# freiBot.net
KiCad netlist of a schematic drawn in EAGLE
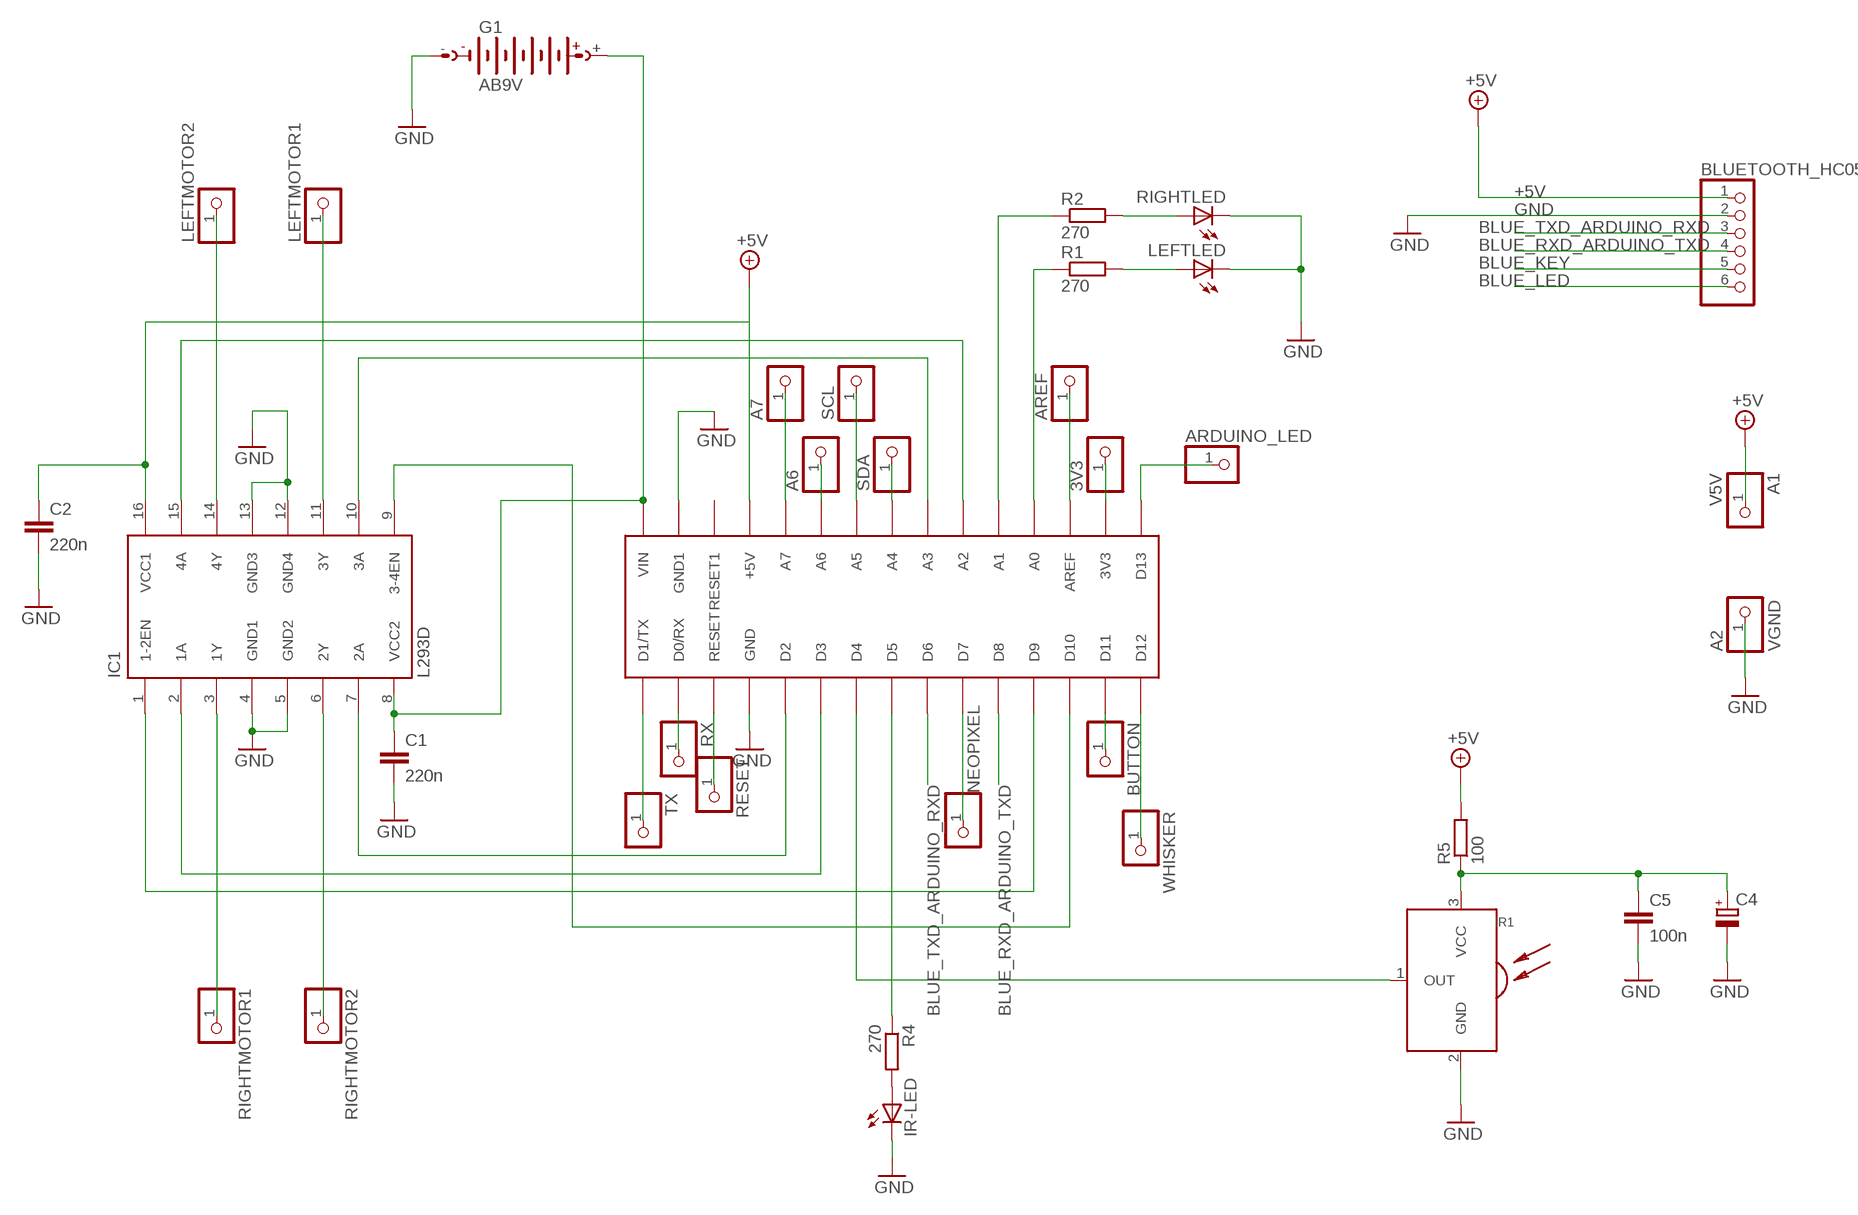
[diagram p0: schematic, sheet 1]

(export (version "E")
  (design (tool "Eeschema 10.0.6"))
  (components
    (comp (ref "3V3")
      (value "PINHD-1X1")
      (footprint "eagle-import:1X01")
      (libsource (lib "eagle-import") (part "PINHD-1X1"))
    )
    (comp (ref "A1")
      (value "V5V")
      (footprint "eagle-import:1X01")
      (libsource (lib "eagle-import") (part "PINHD-1X1"))
    )
    (comp (ref "A2")
      (value "VGND")
      (footprint "eagle-import:1X01")
      (libsource (lib "eagle-import") (part "PINHD-1X1"))
    )
    (comp (ref "A6")
      (value "PINHD-1X1")
      (footprint "eagle-import:1X01")
      (libsource (lib "eagle-import") (part "PINHD-1X1"))
    )
    (comp (ref "A7")
      (value "PINHD-1X1")
      (footprint "eagle-import:1X01")
      (libsource (lib "eagle-import") (part "PINHD-1X1"))
    )
    (comp (ref "ARDUINO_LED")
      (value "PINHD-1X1")
      (footprint "eagle-import:1X01")
      (libsource (lib "eagle-import") (part "PINHD-1X1"))
    )
    (comp (ref "AREF")
      (value "PINHD-1X1")
      (footprint "eagle-import:1X01")
      (libsource (lib "eagle-import") (part "PINHD-1X1"))
    )
    (comp (ref "BLUETOOTH_HC05")
      (value "PINHD-1X6")
      (footprint "eagle-import:1X06")
      (libsource (lib "eagle-import") (part "PINHD-1X6"))
    )
    (comp (ref "BUTTON")
      (value "PINHD-1X1")
      (footprint "eagle-import:1X01")
      (libsource (lib "eagle-import") (part "PINHD-1X1"))
    )
    (comp (ref "C1")
      (value "220n")
      (footprint "eagle-import:C075-042X103")
      (libsource (lib "eagle-import") (part "C-EU075-042X103"))
    )
    (comp (ref "C2")
      (value "220n")
      (footprint "eagle-import:C075-042X103")
      (libsource (lib "eagle-import") (part "C-EU075-042X103"))
    )
    (comp (ref "C4")
      (value "CPOL-EUE5-8.5")
      (footprint "eagle-import:E5-8,5")
      (libsource (lib "eagle-import") (part "CPOL-EUE5-8.5"))
    )
    (comp (ref "C5")
      (value "100n")
      (footprint "eagle-import:C050-025X075")
      (libsource (lib "eagle-import") (part "C-EU050-025X075"))
    )
    (comp (ref "G1")
      (value "AB9V")
      (footprint "eagle-import:AB9V")
      (libsource (lib "eagle-import") (part "AB9V"))
    )
    (comp (ref "IC1")
      (value "L293D")
      (footprint "eagle-import:DIL16")
      (libsource (lib "eagle-import") (part "L293D"))
    )
    (comp (ref "IR-LED")
      (value "LED5MM")
      (footprint "eagle-import:LED5MM")
      (libsource (lib "eagle-import") (part "LED5MM"))
    )
    (comp (ref "IR1")
      (value "SFH5110")
      (footprint "eagle-import:SFH511_")
      (libsource (lib "eagle-import") (part "SFH5110"))
    )
    (comp (ref "LEFTLED")
      (value "LED10MM")
      (footprint "eagle-import:LED10MM")
      (libsource (lib "eagle-import") (part "LED10MM"))
    )
    (comp (ref "LEFTMOTOR1")
      (value "PINHD-1X1")
      (footprint "eagle-import:1X01")
      (libsource (lib "eagle-import") (part "PINHD-1X1"))
    )
    (comp (ref "LEFTMOTOR2")
      (value "PINHD-1X1")
      (footprint "eagle-import:1X01")
      (libsource (lib "eagle-import") (part "PINHD-1X1"))
    )
    (comp (ref "NEOPIXEL")
      (value "PINHD-1X1")
      (footprint "eagle-import:1X01")
      (libsource (lib "eagle-import") (part "PINHD-1X1"))
    )
    (comp (ref "R1")
      (value "270")
      (footprint "eagle-import:0309_12")
      (libsource (lib "eagle-import") (part "R-EU_0309/12"))
    )
    (comp (ref "R2")
      (value "270")
      (footprint "eagle-import:0309_12")
      (libsource (lib "eagle-import") (part "R-EU_0309/12"))
    )
    (comp (ref "R4")
      (value "270")
      (footprint "eagle-import:0309_12")
      (libsource (lib "eagle-import") (part "R-EU_0309/12"))
    )
    (comp (ref "R5")
      (value "100")
      (footprint "eagle-import:0309_10")
      (libsource (lib "eagle-import") (part "R-EU_0309/10"))
    )
    (comp (ref "RESET")
      (value "PINHD-1X1")
      (footprint "eagle-import:1X01")
      (libsource (lib "eagle-import") (part "PINHD-1X1"))
    )
    (comp (ref "RIGHTLED")
      (value "LED10MM")
      (footprint "eagle-import:LED10MM")
      (libsource (lib "eagle-import") (part "LED10MM"))
    )
    (comp (ref "RIGHTMOTOR1")
      (value "PINHD-1X1")
      (footprint "eagle-import:1X01")
      (libsource (lib "eagle-import") (part "PINHD-1X1"))
    )
    (comp (ref "RIGHTMOTOR2")
      (value "PINHD-1X1")
      (footprint "eagle-import:1X01")
      (libsource (lib "eagle-import") (part "PINHD-1X1"))
    )
    (comp (ref "RX")
      (value "PINHD-1X1")
      (footprint "eagle-import:1X01")
      (libsource (lib "eagle-import") (part "PINHD-1X1"))
    )
    (comp (ref "SCL")
      (value "PINHD-1X1")
      (footprint "eagle-import:1X01")
      (libsource (lib "eagle-import") (part "PINHD-1X1"))
    )
    (comp (ref "SDA")
      (value "PINHD-1X1")
      (footprint "eagle-import:1X01")
      (libsource (lib "eagle-import") (part "PINHD-1X1"))
    )
    (comp (ref "TX")
      (value "PINHD-1X1")
      (footprint "eagle-import:1X01")
      (libsource (lib "eagle-import") (part "PINHD-1X1"))
    )
    (comp (ref "U$1")
      (value "ARDUINONANO")
      (footprint "eagle-import:PDIP-32")
      (libsource (lib "eagle-import") (part "ARDUINONANO"))
    )
    (comp (ref "WHISKER")
      (value "PINHD-1X1")
      (footprint "eagle-import:1X01")
      (libsource (lib "eagle-import") (part "PINHD-1X1"))
    )
  )
  (nets
    (net (code "1") (name "+5V") (class "Default")
      (node (ref "A1") (pin "1") (pinfunction "1_1") (pintype "passive"))
      (node (ref "BLUETOOTH_HC05") (pin "1") (pinfunction "1_1") (pintype "passive"))
      (node (ref "C2") (pin "1") (pinfunction "1_1") (pintype "passive"))
      (node (ref "IC1") (pin "16") (pinfunction "VCC1_16") (pintype "power_in"))
      (node (ref "R5") (pin "2") (pinfunction "2_2") (pintype "passive"))
      (node (ref "U$1") (pin "+5V") (pinfunction "+5V_+5V") (pintype "bidirectional"))
    )
    (net (code "2") (name "/BLUE_KEY") (class "Default")
      (node (ref "BLUETOOTH_HC05") (pin "5") (pinfunction "5_5") (pintype "passive"))
    )
    (net (code "3") (name "/BLUE_LED") (class "Default")
      (node (ref "BLUETOOTH_HC05") (pin "6") (pinfunction "6_6") (pintype "passive"))
    )
    (net (code "4") (name "/BLUE_RXD_ARDUINO_TXD") (class "Default")
      (node (ref "BLUETOOTH_HC05") (pin "4") (pinfunction "4_4") (pintype "passive"))
      (node (ref "U$1") (pin "D8") (pinfunction "D8_D8") (pintype "bidirectional"))
    )
    (net (code "5") (name "/BLUE_TXD_ARDUINO_RXD") (class "Default")
      (node (ref "BLUETOOTH_HC05") (pin "3") (pinfunction "3_3") (pintype "passive"))
      (node (ref "U$1") (pin "D6") (pinfunction "D6_D6") (pintype "bidirectional"))
    )
    (net (code "6") (name "GND") (class "Default")
      (node (ref "A2") (pin "1") (pinfunction "1_1") (pintype "passive"))
      (node (ref "BLUETOOTH_HC05") (pin "2") (pinfunction "2_2") (pintype "passive"))
      (node (ref "C1") (pin "2") (pinfunction "2_2") (pintype "passive"))
      (node (ref "C2") (pin "2") (pinfunction "2_2") (pintype "passive"))
      (node (ref "C4") (pin "-") (pinfunction "-_-") (pintype "passive"))
      (node (ref "C5") (pin "2") (pinfunction "2_2") (pintype "passive"))
      (node (ref "G1") (pin "-") (pinfunction "-_-") (pintype "passive"))
      (node (ref "IC1") (pin "12") (pinfunction "GND4_12") (pintype "power_in"))
      (node (ref "IC1") (pin "13") (pinfunction "GND3_13") (pintype "power_in"))
      (node (ref "IC1") (pin "4") (pinfunction "GND1_4") (pintype "power_in"))
      (node (ref "IC1") (pin "5") (pinfunction "GND2_5") (pintype "power_in"))
      (node (ref "IR-LED") (pin "K") (pinfunction "C_K") (pintype "passive"))
      (node (ref "IR1") (pin "2") (pinfunction "GND_2") (pintype "power_in"))
      (node (ref "LEFTLED") (pin "K") (pinfunction "C_K") (pintype "passive"))
      (node (ref "RIGHTLED") (pin "K") (pinfunction "C_K") (pintype "passive"))
      (node (ref "U$1") (pin "GND") (pinfunction "GND_GND") (pintype "bidirectional"))
      (node (ref "U$1") (pin "GND1") (pinfunction "GND1_GND1") (pintype "bidirectional"))
    )
    (net (code "7") (name "Net-(3V3-Pad1)") (class "Default")
      (node (ref "3V3") (pin "1") (pinfunction "1_1") (pintype "passive"))
      (node (ref "U$1") (pin "3V3") (pinfunction "3V3_3V3") (pintype "bidirectional"))
    )
    (net (code "8") (name "Net-(A6-Pad1)") (class "Default")
      (node (ref "A6") (pin "1") (pinfunction "1_1") (pintype "passive"))
      (node (ref "U$1") (pin "A6") (pinfunction "A6_A6") (pintype "bidirectional"))
    )
    (net (code "9") (name "Net-(A7-Pad1)") (class "Default")
      (node (ref "A7") (pin "1") (pinfunction "1_1") (pintype "passive"))
      (node (ref "U$1") (pin "A7") (pinfunction "A7_A7") (pintype "bidirectional"))
    )
    (net (code "10") (name "Net-(ARDUINO_LED-Pad1)") (class "Default")
      (node (ref "ARDUINO_LED") (pin "1") (pinfunction "1_1") (pintype "passive"))
      (node (ref "U$1") (pin "D13") (pinfunction "D13_D13") (pintype "bidirectional"))
    )
    (net (code "11") (name "Net-(AREF-Pad1)") (class "Default")
      (node (ref "AREF") (pin "1") (pinfunction "1_1") (pintype "passive"))
      (node (ref "U$1") (pin "AREF") (pinfunction "AREF_AREF") (pintype "bidirectional"))
    )
    (net (code "12") (name "Net-(BUTTON-Pad1)") (class "Default")
      (node (ref "BUTTON") (pin "1") (pinfunction "1_1") (pintype "passive"))
      (node (ref "U$1") (pin "D11") (pinfunction "D11_D11") (pintype "bidirectional"))
    )
    (net (code "13") (name "Net-(IC1-1-2EN)") (class "Default")
      (node (ref "IC1") (pin "1") (pinfunction "1-2EN_1") (pintype "input"))
      (node (ref "U$1") (pin "D9") (pinfunction "D9_D9") (pintype "bidirectional"))
    )
    (net (code "14") (name "Net-(IC1-1A)") (class "Default")
      (node (ref "IC1") (pin "2") (pinfunction "1A_2") (pintype "input"))
      (node (ref "U$1") (pin "D3") (pinfunction "D3_D3") (pintype "bidirectional"))
    )
    (net (code "15") (name "Net-(IC1-1Y)") (class "Default")
      (node (ref "IC1") (pin "3") (pinfunction "1Y_3") (pintype "output"))
      (node (ref "RIGHTMOTOR1") (pin "1") (pinfunction "1_1") (pintype "passive"))
    )
    (net (code "16") (name "Net-(IC1-2A)") (class "Default")
      (node (ref "IC1") (pin "7") (pinfunction "2A_7") (pintype "input"))
      (node (ref "U$1") (pin "D2") (pinfunction "D2_D2") (pintype "bidirectional"))
    )
    (net (code "17") (name "Net-(IC1-2Y)") (class "Default")
      (node (ref "IC1") (pin "6") (pinfunction "2Y_6") (pintype "output"))
      (node (ref "RIGHTMOTOR2") (pin "1") (pinfunction "1_1") (pintype "passive"))
    )
    (net (code "18") (name "Net-(IC1-3-4EN)") (class "Default")
      (node (ref "IC1") (pin "9") (pinfunction "3-4EN_9") (pintype "input"))
      (node (ref "U$1") (pin "D10") (pinfunction "D10_D10") (pintype "bidirectional"))
    )
    (net (code "19") (name "Net-(IC1-3A)") (class "Default")
      (node (ref "IC1") (pin "10") (pinfunction "3A_10") (pintype "input"))
      (node (ref "U$1") (pin "A3") (pinfunction "A3_A3") (pintype "bidirectional"))
    )
    (net (code "20") (name "Net-(IC1-3Y)") (class "Default")
      (node (ref "IC1") (pin "11") (pinfunction "3Y_11") (pintype "output"))
      (node (ref "LEFTMOTOR1") (pin "1") (pinfunction "1_1") (pintype "passive"))
    )
    (net (code "21") (name "Net-(IC1-4A)") (class "Default")
      (node (ref "IC1") (pin "15") (pinfunction "4A_15") (pintype "input"))
      (node (ref "U$1") (pin "A2") (pinfunction "A2_A2") (pintype "bidirectional"))
    )
    (net (code "22") (name "Net-(IC1-4Y)") (class "Default")
      (node (ref "IC1") (pin "14") (pinfunction "4Y_14") (pintype "output"))
      (node (ref "LEFTMOTOR2") (pin "1") (pinfunction "1_1") (pintype "passive"))
    )
    (net (code "23") (name "Net-(IC1-VCC2)") (class "Default")
      (node (ref "C1") (pin "1") (pinfunction "1_1") (pintype "passive"))
      (node (ref "G1") (pin "+") (pinfunction "+_+") (pintype "passive"))
      (node (ref "IC1") (pin "8") (pinfunction "VCC2_8") (pintype "power_in"))
      (node (ref "U$1") (pin "VIN") (pinfunction "VIN_VIN") (pintype "bidirectional"))
    )
    (net (code "24") (name "Net-(IR-LED-PadA)") (class "Default")
      (node (ref "IR-LED") (pin "A") (pinfunction "A_A") (pintype "passive"))
      (node (ref "R4") (pin "2") (pinfunction "2_2") (pintype "passive"))
    )
    (net (code "25") (name "Net-(IR1-OUT)") (class "Default")
      (node (ref "IR1") (pin "1") (pinfunction "OUT_1") (pintype "output"))
      (node (ref "U$1") (pin "D4") (pinfunction "D4_D4") (pintype "bidirectional"))
    )
    (net (code "26") (name "Net-(IR1-VCC)") (class "Default")
      (node (ref "C4") (pin "+") (pinfunction "+_+") (pintype "passive"))
      (node (ref "C5") (pin "1") (pinfunction "1_1") (pintype "passive"))
      (node (ref "IR1") (pin "3") (pinfunction "VCC_3") (pintype "power_in"))
      (node (ref "R5") (pin "1") (pinfunction "1_1") (pintype "passive"))
    )
    (net (code "27") (name "Net-(LEFTLED-PadA)") (class "Default")
      (node (ref "LEFTLED") (pin "A") (pinfunction "A_A") (pintype "passive"))
      (node (ref "R1") (pin "2") (pinfunction "2_2") (pintype "passive"))
    )
    (net (code "28") (name "Net-(NEOPIXEL-Pad1)") (class "Default")
      (node (ref "NEOPIXEL") (pin "1") (pinfunction "1_1") (pintype "passive"))
      (node (ref "U$1") (pin "D7") (pinfunction "D7_D7") (pintype "bidirectional"))
    )
    (net (code "29") (name "Net-(R1-Pad1)") (class "Default")
      (node (ref "R1") (pin "1") (pinfunction "1_1") (pintype "passive"))
      (node (ref "U$1") (pin "A0") (pinfunction "A0_A0") (pintype "bidirectional"))
    )
    (net (code "30") (name "Net-(R2-Pad1)") (class "Default")
      (node (ref "R2") (pin "1") (pinfunction "1_1") (pintype "passive"))
      (node (ref "U$1") (pin "A1") (pinfunction "A1_A1") (pintype "bidirectional"))
    )
    (net (code "31") (name "Net-(R2-Pad2)") (class "Default")
      (node (ref "R2") (pin "2") (pinfunction "2_2") (pintype "passive"))
      (node (ref "RIGHTLED") (pin "A") (pinfunction "A_A") (pintype "passive"))
    )
    (net (code "32") (name "Net-(R4-Pad1)") (class "Default")
      (node (ref "R4") (pin "1") (pinfunction "1_1") (pintype "passive"))
      (node (ref "U$1") (pin "D5") (pinfunction "D5_D5") (pintype "bidirectional"))
    )
    (net (code "33") (name "Net-(RESET-Pad1)") (class "Default")
      (node (ref "RESET") (pin "1") (pinfunction "1_1") (pintype "passive"))
      (node (ref "U$1") (pin "RESET") (pinfunction "RESET_RESET") (pintype "bidirectional"))
    )
    (net (code "34") (name "Net-(RX-Pad1)") (class "Default")
      (node (ref "RX") (pin "1") (pinfunction "1_1") (pintype "passive"))
      (node (ref "U$1") (pin "D0/RX") (pinfunction "D0/RX_D0/RX") (pintype "bidirectional"))
    )
    (net (code "35") (name "Net-(SCL-Pad1)") (class "Default")
      (node (ref "SCL") (pin "1") (pinfunction "1_1") (pintype "passive"))
      (node (ref "U$1") (pin "A5") (pinfunction "A5_A5") (pintype "bidirectional"))
    )
    (net (code "36") (name "Net-(SDA-Pad1)") (class "Default")
      (node (ref "SDA") (pin "1") (pinfunction "1_1") (pintype "passive"))
      (node (ref "U$1") (pin "A4") (pinfunction "A4_A4") (pintype "bidirectional"))
    )
    (net (code "37") (name "Net-(TX-Pad1)") (class "Default")
      (node (ref "TX") (pin "1") (pinfunction "1_1") (pintype "passive"))
      (node (ref "U$1") (pin "D1/TX") (pinfunction "D1/TX_D1/TX") (pintype "bidirectional"))
    )
    (net (code "38") (name "Net-(U$1-PadD12)") (class "Default")
      (node (ref "U$1") (pin "D12") (pinfunction "D12_D12") (pintype "bidirectional"))
      (node (ref "WHISKER") (pin "1") (pinfunction "1_1") (pintype "passive"))
    )
    (net (code "39") (name "unconnected-(U$1-PadRESET1)") (class "Default")
      (node (ref "U$1") (pin "RESET1") (pinfunction "RESET1_RESET1") (pintype "bidirectional"))
    )
  )
)
